# rx.net
KiCad netlist of a schematic drawn in Altium Designer
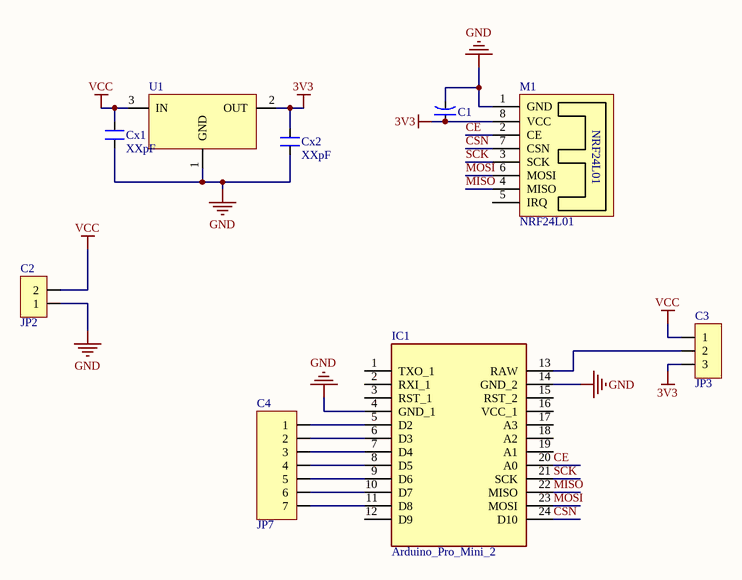
[diagram p0: rx.SchDoc]

(export (version "E")
  (design (tool "Eeschema 10.0.6"))
  (components
    (comp (ref "C1")
      (value "CN-ALU-DIP")
      (footprint "CA-ALU-2.54")
      (description "Capacitor (Semiconductor SIM Model)")
      (fields (field (name "PUBLISHER") "Altium Limited"))
      (libsource (lib "LIBRARY") (part "CN-ALU-DIP"))
    )
    (comp (ref "C2")
      (value "JP2")
      (footprint "JP2-C1T")
      (description "WR-PHD 2.54 mm Angled Socket Header")
      (fields
        (field (name "MANUFACTURER") "Würth Elektronik eiSos GmbH")
        (field (name "PARTNO") "613002143121")
        (field (name "CREATED BY") "Karrer Zheng")
      )
      (libsource (lib "LIBRARY") (part "JP2"))
    )
    (comp (ref "C3")
      (value "JP3")
      (footprint "JP3-CLOSED")
      (description "WR-PHD 2.54 mm Angled Socket Header")
      (fields
        (field (name "MANUFACTURER") "Würth Elektronik eiSos GmbH")
        (field (name "PARTNO") "613003143121")
        (field (name "CREATED BY") "Karrer Zheng")
      )
      (libsource (lib "LIBRARY") (part "JP3"))
    )
    (comp (ref "C4")
      (value "JP7")
      (footprint "JP7-C1T")
      (description "WR-PHD 2.54 mm Angled Socket Header")
      (fields
        (field (name "MANUFACTURER") "Würth Elektronik eiSos GmbH")
        (field (name "PARTNO") "613007143121")
        (field (name "CREATED BY") "Karrer Zheng")
      )
      (libsource (lib "LIBRARY") (part "JP7"))
    )
    (comp (ref "Cx1") (value "XXpF") (footprint "CN-SMD-1206") (libsource (lib "LIBRARY") (part "CN")))
    (comp (ref "Cx2") (value "XXpF") (footprint "CN-SMD-1206") (libsource (lib "LIBRARY") (part "CN")))
    (comp (ref "IC1")
      (value "Arduino_Pro_Mini_2")
      (footprint "ARDPROMINI 2")
      (description "Integrated Circuit")
      (fields
        (field (name "MANUFACTURER_PART_NUMBER") "ARD-PRO-MINI-5")
        (field (name "MOUSER PART NUMBER") "992-ARD-PRO-MINI-5")
      )
      (libsource (lib "0503") (part "Arduino_Pro_Mini_2"))
    )
    (comp (ref "M1") (value "NRF24L01") (footprint "NRF24L01") (libsource (lib "LIBRARY") (part "NRF24L01")))
    (comp (ref "U1")
      (value "LM1117-3.3V")
      (footprint "SOT223")
      (description "800mA Low-Dropout Linear Regulator")
      (fields (field (name "CREATOR") "Nguyen Ba Bien"))
      (libsource (lib "LIBRARY") (part "LM1117"))
    )
  )
  (nets
    (net (code "1") (name "/CE") (class "Default")
      (node (ref "IC1") (pin "20") (pinfunction "A0_20") (pintype "passive"))
      (node (ref "M1") (pin "2") (pinfunction "CE_2") (pintype "passive"))
    )
    (net (code "2") (name "/CSN") (class "Default")
      (node (ref "IC1") (pin "24") (pinfunction "D10_24") (pintype "passive"))
      (node (ref "M1") (pin "7") (pinfunction "CSN_7") (pintype "passive"))
    )
    (net (code "3") (name "/MISO") (class "Default")
      (node (ref "IC1") (pin "22") (pinfunction "MISO_22") (pintype "passive"))
      (node (ref "M1") (pin "4") (pinfunction "MISO_4") (pintype "passive"))
    )
    (net (code "4") (name "/MOSI") (class "Default")
      (node (ref "IC1") (pin "23") (pinfunction "MOSI_23") (pintype "passive"))
      (node (ref "M1") (pin "6") (pinfunction "MOSI_6") (pintype "passive"))
    )
    (net (code "5") (name "/SCK") (class "Default")
      (node (ref "IC1") (pin "21") (pinfunction "SCK_21") (pintype "passive"))
      (node (ref "M1") (pin "3") (pinfunction "SCK_3") (pintype "passive"))
    )
    (net (code "6") (name "3V3") (class "Default")
      (node (ref "C1") (pin "1") (pinfunction "1_1") (pintype "passive"))
      (node (ref "C3") (pin "3") (pinfunction "3_3") (pintype "passive"))
      (node (ref "Cx2") (pin "2") (pinfunction "2_2") (pintype "passive"))
      (node (ref "M1") (pin "8") (pinfunction "VCC_8") (pintype "passive"))
      (node (ref "U1") (pin "2") (pinfunction "OUT_2") (pintype "passive"))
    )
    (net (code "7") (name "GND") (class "Default")
      (node (ref "C1") (pin "2") (pinfunction "2_2") (pintype "passive"))
      (node (ref "C2") (pin "1") (pinfunction "1_1") (pintype "passive"))
      (node (ref "Cx1") (pin "1") (pinfunction "1_1") (pintype "passive"))
      (node (ref "Cx2") (pin "1") (pinfunction "1_1") (pintype "passive"))
      (node (ref "IC1") (pin "14") (pinfunction "GND_2_14") (pintype "passive"))
      (node (ref "IC1") (pin "4") (pinfunction "GND_1_4") (pintype "passive"))
      (node (ref "M1") (pin "1") (pinfunction "GND_1") (pintype "passive"))
      (node (ref "U1") (pin "1") (pinfunction "GND_1") (pintype "passive"))
    )
    (net (code "8") (name "Net-(IC1-D2)") (class "Default")
      (node (ref "C4") (pin "1") (pinfunction "1_1") (pintype "passive"))
      (node (ref "IC1") (pin "5") (pinfunction "D2_5") (pintype "passive"))
    )
    (net (code "9") (name "Net-(IC1-D3)") (class "Default")
      (node (ref "C4") (pin "2") (pinfunction "2_2") (pintype "passive"))
      (node (ref "IC1") (pin "6") (pinfunction "D3_6") (pintype "passive"))
    )
    (net (code "10") (name "Net-(IC1-D4)") (class "Default")
      (node (ref "C4") (pin "3") (pinfunction "3_3") (pintype "passive"))
      (node (ref "IC1") (pin "7") (pinfunction "D4_7") (pintype "passive"))
    )
    (net (code "11") (name "Net-(IC1-D5)") (class "Default")
      (node (ref "C4") (pin "4") (pinfunction "4_4") (pintype "passive"))
      (node (ref "IC1") (pin "8") (pinfunction "D5_8") (pintype "passive"))
    )
    (net (code "12") (name "Net-(IC1-D6)") (class "Default")
      (node (ref "C4") (pin "5") (pinfunction "5_5") (pintype "passive"))
      (node (ref "IC1") (pin "9") (pinfunction "D6_9") (pintype "passive"))
    )
    (net (code "13") (name "Net-(IC1-D7)") (class "Default")
      (node (ref "C4") (pin "6") (pinfunction "6_6") (pintype "passive"))
      (node (ref "IC1") (pin "10") (pinfunction "D7_10") (pintype "passive"))
    )
    (net (code "14") (name "Net-(IC1-D8)") (class "Default")
      (node (ref "C4") (pin "7") (pinfunction "7_7") (pintype "passive"))
      (node (ref "IC1") (pin "11") (pinfunction "D8_11") (pintype "passive"))
    )
    (net (code "15") (name "Net-(IC1-RAW)") (class "Default")
      (node (ref "C3") (pin "2") (pinfunction "2_2") (pintype "passive"))
      (node (ref "IC1") (pin "13") (pinfunction "RAW_13") (pintype "passive"))
    )
    (net (code "16") (name "VCC") (class "Default")
      (node (ref "C2") (pin "2") (pinfunction "2_2") (pintype "passive"))
      (node (ref "C3") (pin "1") (pinfunction "1_1") (pintype "passive"))
      (node (ref "Cx1") (pin "2") (pinfunction "2_2") (pintype "passive"))
      (node (ref "U1") (pin "3") (pinfunction "IN_3") (pintype "passive"))
    )
    (net (code "17") (name "unconnected-(IC1-A1-Pad19)") (class "Default")
      (node (ref "IC1") (pin "19") (pinfunction "A1_19") (pintype "passive"))
    )
    (net (code "18") (name "unconnected-(IC1-A2-Pad18)") (class "Default")
      (node (ref "IC1") (pin "18") (pinfunction "A2_18") (pintype "passive"))
    )
    (net (code "19") (name "unconnected-(IC1-A3-Pad17)") (class "Default")
      (node (ref "IC1") (pin "17") (pinfunction "A3_17") (pintype "passive"))
    )
    (net (code "20") (name "unconnected-(IC1-D9-Pad12)") (class "Default")
      (node (ref "IC1") (pin "12") (pinfunction "D9_12") (pintype "passive"))
    )
    (net (code "21") (name "unconnected-(IC1-RST_1-Pad3)") (class "Default")
      (node (ref "IC1") (pin "3") (pinfunction "RST_1_3") (pintype "passive"))
    )
    (net (code "22") (name "unconnected-(IC1-RST_2-Pad15)") (class "Default")
      (node (ref "IC1") (pin "15") (pinfunction "RST_2_15") (pintype "passive"))
    )
    (net (code "23") (name "unconnected-(IC1-RXI_1-Pad2)") (class "Default")
      (node (ref "IC1") (pin "2") (pinfunction "RXI_1_2") (pintype "passive"))
    )
    (net (code "24") (name "unconnected-(IC1-TXO_1-Pad1)") (class "Default")
      (node (ref "IC1") (pin "1") (pinfunction "TXO_1_1") (pintype "passive"))
    )
    (net (code "25") (name "unconnected-(IC1-VCC_1-Pad16)") (class "Default")
      (node (ref "IC1") (pin "16") (pinfunction "VCC_1_16") (pintype "passive"))
    )
    (net (code "26") (name "unconnected-(M1-IRQ-Pad5)") (class "Default")
      (node (ref "M1") (pin "5") (pinfunction "IRQ_5") (pintype "passive"))
    )
  )
)
